# Akcelerometar.net
KiCad netlist of a schematic drawn in Altium Designer
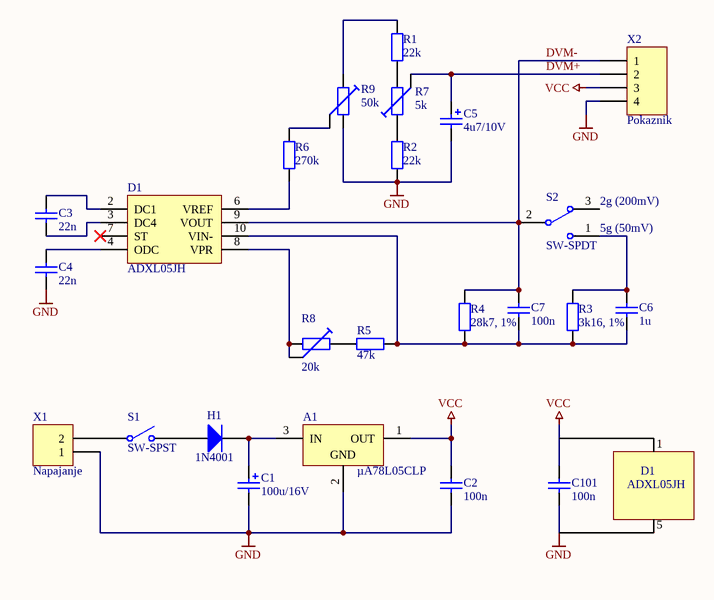
[diagram p0: Akcelerometar.SchDoc]

(export (version "E")
  (design (tool "Eeschema 10.0.6"))
  (components
    (comp (ref "A1")
      (value "µA78L05CLP")
      (footprint "LP03")
      (description "Positive-Voltage Regulator")
      (fields (field (name "PUBLISHER") "Altium Limited"))
      (libsource (lib "TI Power Mgt Voltage Regulator") (part "µA78L05CLP"))
    )
    (comp (ref "C1")
      (value "100u/16V")
      (footprint "CAPPR2-5x11")
      (description "Polarized Capacitor (Axial)")
      (fields (field (name "PUBLISHER") "Altium Limited"))
      (libsource (lib "Miscellaneous Devices") (part "Cap Pol2"))
    )
    (comp (ref "C2")
      (value "100n")
      (footprint "RAD-0.1")
      (description "Capacitor")
      (fields (field (name "PUBLISHER") "Altium Limited"))
      (libsource (lib "Miscellaneous Devices") (part "Cap"))
    )
    (comp (ref "C3")
      (value "22n")
      (footprint "RAD-0.1")
      (description "Capacitor")
      (fields (field (name "PUBLISHER") "Altium Limited"))
      (libsource (lib "Miscellaneous Devices") (part "Cap"))
    )
    (comp (ref "C4")
      (value "22n")
      (footprint "RAD-0.1")
      (description "Capacitor")
      (fields (field (name "PUBLISHER") "Altium Limited"))
      (libsource (lib "Miscellaneous Devices") (part "Cap"))
    )
    (comp (ref "C5")
      (value "4u7/10V")
      (footprint "CAPPR2-5x11")
      (description "Polarized Capacitor (Axial)")
      (fields (field (name "PUBLISHER") "Altium Limited"))
      (libsource (lib "Miscellaneous Devices") (part "Cap Pol2"))
    )
    (comp (ref "C6")
      (value "1u")
      (footprint "RAD-0.1")
      (description "Capacitor")
      (fields (field (name "PUBLISHER") "Altium Limited"))
      (libsource (lib "Miscellaneous Devices") (part "Cap"))
    )
    (comp (ref "C7")
      (value "100n")
      (footprint "RAD-0.1")
      (description "Capacitor")
      (fields (field (name "PUBLISHER") "Altium Limited"))
      (libsource (lib "Miscellaneous Devices") (part "Cap"))
    )
    (comp (ref "C101")
      (value "100n")
      (footprint "RAD-0.1")
      (description "Capacitor")
      (fields (field (name "PUBLISHER") "Altium Limited"))
      (libsource (lib "Miscellaneous Devices") (part "Cap"))
    )
    (comp (ref "D1") (value "ADXL05JH") (footprint "ADXL05") (libsource (lib "Lab1") (part "ADXL05JH")))
    (comp (ref "H1")
      (value "1N4001")
      (footprint "SMC")
      (description "Default Diode")
      (fields (field (name "PUBLISHER") "Altium Limited"))
      (libsource (lib "Miscellaneous Devices") (part "Diode"))
    )
    (comp (ref "R1")
      (value "22k")
      (footprint "AXIAL-0.4")
      (description "Resistor")
      (fields (field (name "PUBLISHER") "Altium Limited"))
      (libsource (lib "") (part "Res2_1"))
    )
    (comp (ref "R2")
      (value "22k")
      (footprint "AXIAL-0.4")
      (description "Resistor")
      (fields (field (name "PUBLISHER") "Altium Limited"))
      (libsource (lib "") (part "Res2_1"))
    )
    (comp (ref "R3")
      (value "3k16, 1%")
      (footprint "AXIAL-0.4")
      (description "Resistor")
      (fields (field (name "PUBLISHER") "Altium Limited"))
      (libsource (lib "") (part "Res2_1"))
    )
    (comp (ref "R4")
      (value "28k7, 1%")
      (footprint "AXIAL-0.4")
      (description "Resistor")
      (fields (field (name "PUBLISHER") "Altium Limited"))
      (libsource (lib "") (part "Res2_1"))
    )
    (comp (ref "R5")
      (value "47k")
      (footprint "AXIAL-0.4")
      (description "Resistor")
      (fields (field (name "PUBLISHER") "Altium Limited"))
      (libsource (lib "Miscellaneous Devices") (part "Res2"))
    )
    (comp (ref "R6")
      (value "270k")
      (footprint "AXIAL-0.4")
      (description "Resistor")
      (fields (field (name "PUBLISHER") "Altium Limited"))
      (libsource (lib "") (part "Res2_1"))
    )
    (comp (ref "R7") (value "5k") (footprint "VR2") (libsource (lib "Lab1") (part "Trimmer")))
    (comp (ref "R8") (value "20k") (footprint "VR2") (libsource (lib "Lab1") (part "Trimmer")))
    (comp (ref "R9") (value "50k") (footprint "VR2") (libsource (lib "Lab1") (part "Trimmer")))
    (comp (ref "S1")
      (value "SW-SPST")
      (footprint "TOOGLE")
      (description "Single-Pole, Single-Throw Switch")
      (fields (field (name "PUBLISHER") "Altium Limited"))
      (libsource (lib "Miscellaneous Devices") (part "SW-SPST"))
    )
    (comp (ref "S2")
      (value "SW-SPDT")
      (footprint "TOOGLE")
      (description "SPDT Subminiature Toggle Switch, Right Angle Mounting, Vertical Actuation")
      (fields (field (name "PUBLISHER") "Altium Limited"))
      (libsource (lib "Miscellaneous Devices") (part "SW-SPDT"))
    )
    (comp (ref "X1")
      (value "Napajanje")
      (footprint "HDR1X2")
      (description "Header, 2-Pin")
      (fields (field (name "PUBLISHER") "Altium Limited"))
      (libsource (lib "Miscellaneous Connectors") (part "Header 2"))
    )
    (comp (ref "X2")
      (value "Pokaznik")
      (footprint "HDR1X4")
      (description "Header, 4-Pin")
      (fields (field (name "PUBLISHER") "Altium Limited"))
      (libsource (lib "Miscellaneous Connectors") (part "Header 4"))
    )
  )
  (nets
    (net (code "1") (name "/DVM+") (class "Default")
      (node (ref "C5") (pin "1") (pinfunction "1_1") (pintype "passive"))
      (node (ref "R7") (pin "2") (pinfunction "2_2") (pintype "passive"))
      (node (ref "X2") (pin "2") (pinfunction "2_2") (pintype "passive"))
    )
    (net (code "2") (name "/DVM-") (class "Default")
      (node (ref "C7") (pin "2") (pinfunction "2_2") (pintype "passive"))
      (node (ref "D1") (pin "9") (pinfunction "VOUT_9") (pintype "passive"))
      (node (ref "R4") (pin "2") (pinfunction "2_2") (pintype "passive"))
      (node (ref "S2") (pin "2") (pinfunction "2_2") (pintype "passive"))
      (node (ref "X2") (pin "1") (pinfunction "1_1") (pintype "passive"))
    )
    (net (code "3") (name "GND") (class "Default")
      (node (ref "A1") (pin "2") (pinfunction "GND_2") (pintype "power_in"))
      (node (ref "C1") (pin "2") (pinfunction "2_2") (pintype "passive"))
      (node (ref "C101") (pin "1") (pinfunction "1_1") (pintype "passive"))
      (node (ref "C2") (pin "1") (pinfunction "1_1") (pintype "passive"))
      (node (ref "C4") (pin "2") (pinfunction "2_2") (pintype "passive"))
      (node (ref "C5") (pin "2") (pinfunction "2_2") (pintype "passive"))
      (node (ref "D1") (pin "5") (pinfunction "GND_5") (pintype "power_in"))
      (node (ref "R2") (pin "1") (pinfunction "1_1") (pintype "passive"))
      (node (ref "R9") (pin "3") (pinfunction "3_3") (pintype "passive"))
      (node (ref "X1") (pin "1") (pinfunction "1_1") (pintype "passive"))
      (node (ref "X2") (pin "4") (pinfunction "4_4") (pintype "passive"))
    )
    (net (code "4") (name "Net-(A1-IN)") (class "Default")
      (node (ref "A1") (pin "3") (pinfunction "IN_3") (pintype "power_in"))
      (node (ref "C1") (pin "1") (pinfunction "1_1") (pintype "passive"))
      (node (ref "H1") (pin "2") (pinfunction "K_2") (pintype "passive"))
    )
    (net (code "5") (name "Net-(C6-Pad2)") (class "Default")
      (node (ref "C6") (pin "2") (pinfunction "2_2") (pintype "passive"))
      (node (ref "R3") (pin "2") (pinfunction "2_2") (pintype "passive"))
      (node (ref "S2") (pin "1") (pinfunction "1_1") (pintype "passive"))
    )
    (net (code "6") (name "Net-(D1-DC1)") (class "Default")
      (node (ref "C3") (pin "2") (pinfunction "2_2") (pintype "passive"))
      (node (ref "D1") (pin "2") (pinfunction "DC1_2") (pintype "passive"))
    )
    (net (code "7") (name "Net-(D1-DC4)") (class "Default")
      (node (ref "C3") (pin "1") (pinfunction "1_1") (pintype "passive"))
      (node (ref "D1") (pin "3") (pinfunction "DC4_3") (pintype "passive"))
    )
    (net (code "8") (name "Net-(D1-ODC)") (class "Default")
      (node (ref "C4") (pin "1") (pinfunction "1_1") (pintype "passive"))
      (node (ref "D1") (pin "4") (pinfunction "ODC_4") (pintype "passive"))
    )
    (net (code "9") (name "Net-(D1-VIN-)") (class "Default")
      (node (ref "C6") (pin "1") (pinfunction "1_1") (pintype "passive"))
      (node (ref "C7") (pin "1") (pinfunction "1_1") (pintype "passive"))
      (node (ref "D1") (pin "10") (pinfunction "VIN-_10") (pintype "passive"))
      (node (ref "R3") (pin "1") (pinfunction "1_1") (pintype "passive"))
      (node (ref "R4") (pin "1") (pinfunction "1_1") (pintype "passive"))
      (node (ref "R5") (pin "2") (pinfunction "2_2") (pintype "passive"))
    )
    (net (code "10") (name "Net-(D1-VPR)") (class "Default")
      (node (ref "D1") (pin "8") (pinfunction "VPR_8") (pintype "passive"))
      (node (ref "R8") (pin "2") (pinfunction "2_2") (pintype "passive"))
      (node (ref "R8") (pin "3") (pinfunction "3_3") (pintype "passive"))
    )
    (net (code "11") (name "Net-(D1-VREF)") (class "Default")
      (node (ref "D1") (pin "6") (pinfunction "VREF_6") (pintype "passive"))
      (node (ref "R6") (pin "1") (pinfunction "1_1") (pintype "passive"))
    )
    (net (code "12") (name "Net-(H1-A)") (class "Default")
      (node (ref "H1") (pin "1") (pinfunction "A_1") (pintype "passive"))
      (node (ref "S1") (pin "2") (pinfunction "NO_2") (pintype "passive"))
    )
    (net (code "13") (name "Net-(R1-Pad1)") (class "Default")
      (node (ref "R1") (pin "1") (pinfunction "1_1") (pintype "passive"))
      (node (ref "R7") (pin "3") (pinfunction "3_3") (pintype "passive"))
    )
    (net (code "14") (name "Net-(R1-Pad2)") (class "Default")
      (node (ref "R1") (pin "2") (pinfunction "2_2") (pintype "passive"))
      (node (ref "R9") (pin "1") (pinfunction "1_1") (pintype "passive"))
    )
    (net (code "15") (name "Net-(R2-Pad2)") (class "Default")
      (node (ref "R2") (pin "2") (pinfunction "2_2") (pintype "passive"))
      (node (ref "R7") (pin "1") (pinfunction "1_1") (pintype "passive"))
    )
    (net (code "16") (name "Net-(R5-Pad1)") (class "Default")
      (node (ref "R5") (pin "1") (pinfunction "1_1") (pintype "passive"))
      (node (ref "R8") (pin "1") (pinfunction "1_1") (pintype "passive"))
    )
    (net (code "17") (name "Net-(R6-Pad2)") (class "Default")
      (node (ref "R6") (pin "2") (pinfunction "2_2") (pintype "passive"))
      (node (ref "R9") (pin "2") (pinfunction "2_2") (pintype "passive"))
    )
    (net (code "18") (name "Net-(S1-COMMON)") (class "Default")
      (node (ref "S1") (pin "1") (pinfunction "COMMON_1") (pintype "passive"))
      (node (ref "X1") (pin "2") (pinfunction "2_2") (pintype "passive"))
    )
    (net (code "19") (name "VCC") (class "Default")
      (node (ref "A1") (pin "1") (pinfunction "OUT_1") (pintype "power_in"))
      (node (ref "C101") (pin "2") (pinfunction "2_2") (pintype "passive"))
      (node (ref "C2") (pin "2") (pinfunction "2_2") (pintype "passive"))
      (node (ref "D1") (pin "1") (pinfunction "VCC_1") (pintype "power_in"))
      (node (ref "X2") (pin "3") (pinfunction "3_3") (pintype "passive"))
    )
    (net (code "20") (name "unconnected-(D1-ST-Pad7)") (class "Default")
      (node (ref "D1") (pin "7") (pinfunction "ST_7") (pintype "passive+no_connect"))
    )
    (net (code "21") (name "unconnected-(S2-Pad3)") (class "Default")
      (node (ref "S2") (pin "3") (pinfunction "3_3") (pintype "passive"))
    )
  )
)
